# M48_CORE.net
KiCad netlist of a schematic drawn in Altium Designer
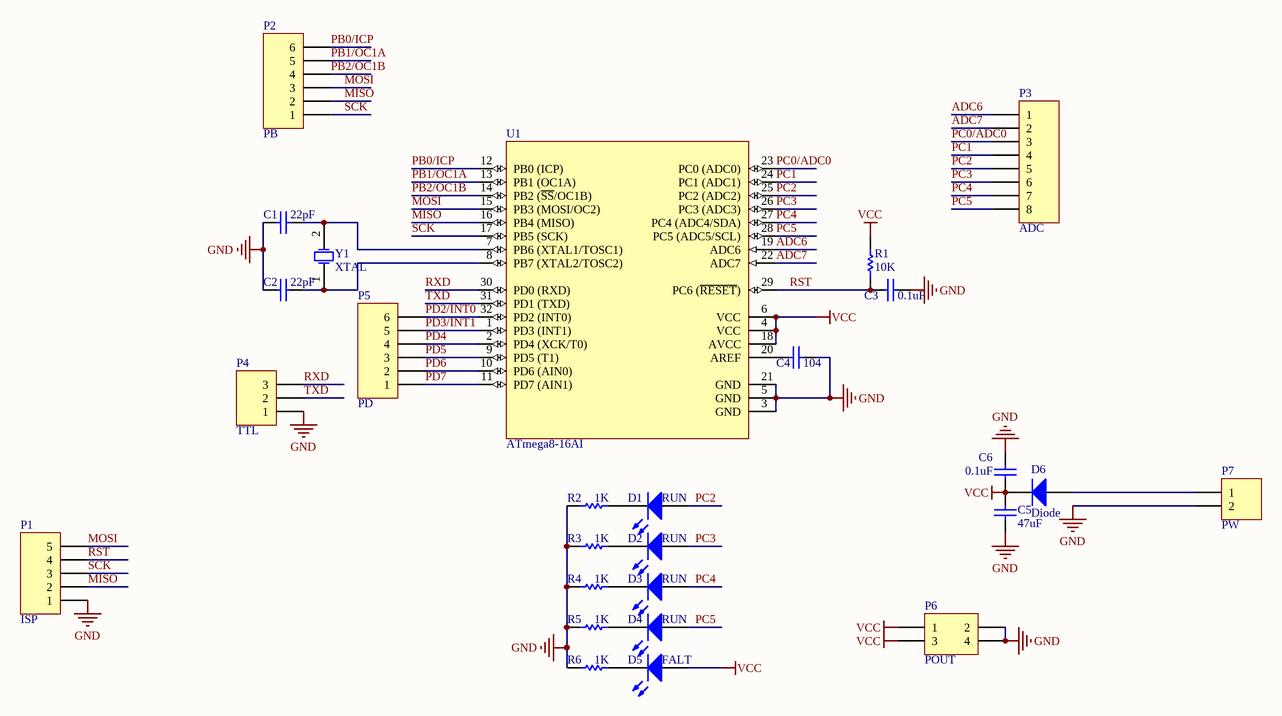
[diagram p0: M48_CORE.SchDoc]

(export (version "E")
  (design (tool "Eeschema 10.0.6"))
  (components
    (comp (ref "C1")
      (value "22pF")
      (footprint "0603")
      (description "Capacitor")
      (fields (field (name "Comment") "Cap") (field (name "PUBLISHER") "Altium Limited"))
      (libsource (lib "Miscellaneous Devices") (part "Cap"))
    )
    (comp (ref "C2")
      (value "22pF")
      (footprint "0603")
      (description "Capacitor")
      (fields (field (name "Comment") "Cap") (field (name "PUBLISHER") "Altium Limited"))
      (libsource (lib "Miscellaneous Devices") (part "Cap"))
    )
    (comp (ref "C3")
      (value "0.1uF")
      (footprint "0603")
      (description "Capacitor")
      (fields (field (name "Comment") "Cap") (field (name "PUBLISHER") "Altium Limited"))
      (libsource (lib "Miscellaneous Devices") (part "Cap"))
    )
    (comp (ref "C4")
      (value "104")
      (footprint "0603")
      (description "Capacitor")
      (fields (field (name "Comment") "Cap") (field (name "PUBLISHER") "Altium Limited"))
      (libsource (lib "Miscellaneous Devices") (part "Cap"))
    )
    (comp (ref "C5")
      (value "47uF")
      (footprint "3216[1206]")
      (description "Capacitor")
      (fields (field (name "Comment") "Cap") (field (name "PUBLISHER") "Altium Limited"))
      (libsource (lib "Miscellaneous Devices") (part "Cap"))
    )
    (comp (ref "C6")
      (value "0.1uF")
      (footprint "0603")
      (description "Capacitor")
      (fields (field (name "Comment") "Cap") (field (name "PUBLISHER") "Altium Limited"))
      (libsource (lib "Miscellaneous Devices") (part "Cap"))
    )
    (comp (ref "D1")
      (value "RUN")
      (footprint "0603-LED")
      (description "Typical RED, GREEN, YELLOW, AMBER GaAs LED")
      (fields (field (name "PUBLISHER") "Altium Limited"))
      (libsource (lib "Miscellaneous Devices") (part "LED2"))
    )
    (comp (ref "D2")
      (value "RUN")
      (footprint "0603-LED")
      (description "Typical RED, GREEN, YELLOW, AMBER GaAs LED")
      (fields (field (name "PUBLISHER") "Altium Limited"))
      (libsource (lib "Miscellaneous Devices") (part "LED2"))
    )
    (comp (ref "D3")
      (value "RUN")
      (footprint "0603-LED")
      (description "Typical RED, GREEN, YELLOW, AMBER GaAs LED")
      (fields (field (name "PUBLISHER") "Altium Limited"))
      (libsource (lib "Miscellaneous Devices") (part "LED2"))
    )
    (comp (ref "D4")
      (value "RUN")
      (footprint "0603-LED")
      (description "Typical RED, GREEN, YELLOW, AMBER GaAs LED")
      (fields (field (name "PUBLISHER") "Altium Limited"))
      (libsource (lib "Miscellaneous Devices") (part "LED2"))
    )
    (comp (ref "D5")
      (value "FALT")
      (footprint "0603-LED")
      (description "Typical RED, GREEN, YELLOW, AMBER GaAs LED")
      (fields (field (name "PUBLISHER") "Altium Limited"))
      (libsource (lib "Miscellaneous Devices") (part "LED2"))
    )
    (comp (ref "D6")
      (value "Diode")
      (footprint "SMA")
      (description "Default Diode")
      (fields (field (name "PUBLISHER") "Altium Limited"))
      (libsource (lib "Miscellaneous Devices") (part "Diode"))
    )
    (comp (ref "P1")
      (value "ISP")
      (footprint "HDR1X5")
      (description "Header, 5-Pin")
      (fields (field (name "PUBLISHER") "Altium Limited"))
      (libsource (lib "Miscellaneous Connectors") (part "Header 5"))
    )
    (comp (ref "P2")
      (value "PB")
      (footprint "HDR1X6")
      (description "Header, 6-Pin")
      (fields (field (name "PUBLISHER") "Altium Limited"))
      (libsource (lib "Miscellaneous Connectors") (part "Header 6"))
    )
    (comp (ref "P3")
      (value "ADC")
      (footprint "HDR1X8")
      (description "Header, 8-Pin")
      (fields (field (name "PUBLISHER") "Altium Limited"))
      (libsource (lib "Miscellaneous Connectors") (part "Header 8"))
    )
    (comp (ref "P4")
      (value "TTL")
      (footprint "HDR1X3")
      (description "Header, 3-Pin")
      (fields (field (name "PUBLISHER") "Altium Limited"))
      (libsource (lib "Miscellaneous Connectors") (part "Header 3"))
    )
    (comp (ref "P5")
      (value "PD")
      (footprint "HDR1X6")
      (description "Header, 6-Pin")
      (fields (field (name "PUBLISHER") "Altium Limited"))
      (libsource (lib "Miscellaneous Connectors") (part "Header 6"))
    )
    (comp (ref "P6")
      (value "POUT")
      (footprint "HDR2X2")
      (description "Header, 2-Pin, Dual row, Right Angle")
      (fields (field (name "PUBLISHER") "Altium Limited"))
      (libsource (lib "Miscellaneous Connectors") (part "Header 2X2H"))
    )
    (comp (ref "P7")
      (value "PW")
      (footprint "XH2.54-2P")
      (description "Header, 2-Pin")
      (fields (field (name "PUBLISHER") "Altium Limited"))
      (libsource (lib "Miscellaneous Connectors") (part "Header 2"))
    )
    (comp (ref "R1")
      (value "10K")
      (footprint "0603")
      (description "Resistor")
      (fields (field (name "Comment") "Res1") (field (name "PUBLISHER") "Altium Limited"))
      (libsource (lib "Miscellaneous Devices") (part "Res1"))
    )
    (comp (ref "R2")
      (value "1K")
      (footprint "0603")
      (description "Resistor")
      (fields (field (name "Comment") "Res1") (field (name "PUBLISHER") "Altium Limited"))
      (libsource (lib "Miscellaneous Devices") (part "Res1"))
    )
    (comp (ref "R3")
      (value "1K")
      (footprint "0603")
      (description "Resistor")
      (fields (field (name "Comment") "Res1") (field (name "PUBLISHER") "Altium Limited"))
      (libsource (lib "Miscellaneous Devices") (part "Res1"))
    )
    (comp (ref "R4")
      (value "1K")
      (footprint "0603")
      (description "Resistor")
      (fields (field (name "Comment") "Res1") (field (name "PUBLISHER") "Altium Limited"))
      (libsource (lib "Miscellaneous Devices") (part "Res1"))
    )
    (comp (ref "R5")
      (value "1K")
      (footprint "0603")
      (description "Resistor")
      (fields (field (name "Comment") "Res1") (field (name "PUBLISHER") "Altium Limited"))
      (libsource (lib "Miscellaneous Devices") (part "Res1"))
    )
    (comp (ref "R6")
      (value "1K")
      (footprint "0603")
      (description "Resistor")
      (fields (field (name "Comment") "Res1") (field (name "PUBLISHER") "Altium Limited"))
      (libsource (lib "Miscellaneous Devices") (part "Res1"))
    )
    (comp (ref "U1")
      (value "ATmega8-16AI")
      (footprint "32A_N")
      (description "8-Bit AVR Microcontroller with 8K Bytes of In-System Programmable Flash Memory")
      (fields (field (name "PUBLISHER") "Altium Limited"))
      (libsource (lib "Atmel Microcontroller 8-Bit AVR") (part "ATmega8-16AI"))
    )
    (comp (ref "Y1")
      (value "XTAL")
      (footprint "XT5032")
      (description "Crystal Oscillator")
      (fields (field (name "PUBLISHER") "Altium Limited"))
      (libsource (lib "Miscellaneous Devices") (part "XTAL"))
    )
  )
  (nets
    (net (code "1") (name "/ADC6") (class "Default")
      (node (ref "P3") (pin "1") (pinfunction "1_1") (pintype "passive"))
      (node (ref "U1") (pin "19") (pinfunction "ADC6_19") (pintype "input"))
    )
    (net (code "2") (name "/ADC7") (class "Default")
      (node (ref "P3") (pin "2") (pinfunction "2_2") (pintype "passive"))
      (node (ref "U1") (pin "22") (pinfunction "ADC7_22") (pintype "input"))
    )
    (net (code "3") (name "/MISO") (class "Default")
      (node (ref "P1") (pin "2") (pinfunction "2_2") (pintype "passive"))
      (node (ref "P2") (pin "2") (pinfunction "2_2") (pintype "passive"))
      (node (ref "U1") (pin "16") (pinfunction "PB4_(MISO)_16") (pintype "bidirectional"))
    )
    (net (code "4") (name "/MOSI") (class "Default")
      (node (ref "P1") (pin "5") (pinfunction "5_5") (pintype "passive"))
      (node (ref "P2") (pin "3") (pinfunction "3_3") (pintype "passive"))
      (node (ref "U1") (pin "15") (pinfunction "PB3_(MOSI/OC2)_15") (pintype "bidirectional"))
    )
    (net (code "5") (name "/PB0{slash}ICP") (class "Default")
      (node (ref "P2") (pin "6") (pinfunction "6_6") (pintype "passive"))
      (node (ref "U1") (pin "12") (pinfunction "PB0_(ICP)_12") (pintype "bidirectional"))
    )
    (net (code "6") (name "/PB1{slash}OC1A") (class "Default")
      (node (ref "P2") (pin "5") (pinfunction "5_5") (pintype "passive"))
      (node (ref "U1") (pin "13") (pinfunction "PB1_(OC1A)_13") (pintype "bidirectional"))
    )
    (net (code "7") (name "/PB2{slash}OC1B") (class "Default")
      (node (ref "P2") (pin "4") (pinfunction "4_4") (pintype "passive"))
      (node (ref "U1") (pin "14") (pinfunction "PB2_(~{SS}/OC1B)_14") (pintype "bidirectional"))
    )
    (net (code "8") (name "/PC0{slash}ADC0") (class "Default")
      (node (ref "P3") (pin "3") (pinfunction "3_3") (pintype "passive"))
      (node (ref "U1") (pin "23") (pinfunction "PC0_(ADC0)_23") (pintype "bidirectional"))
    )
    (net (code "9") (name "/PC1") (class "Default")
      (node (ref "P3") (pin "4") (pinfunction "4_4") (pintype "passive"))
      (node (ref "U1") (pin "24") (pinfunction "PC1_(ADC1)_24") (pintype "bidirectional"))
    )
    (net (code "10") (name "/PC2") (class "Default")
      (node (ref "D1") (pin "1") (pinfunction "A_1") (pintype "passive"))
      (node (ref "P3") (pin "5") (pinfunction "5_5") (pintype "passive"))
      (node (ref "U1") (pin "25") (pinfunction "PC2_(ADC2)_25") (pintype "bidirectional"))
    )
    (net (code "11") (name "/PC3") (class "Default")
      (node (ref "D2") (pin "1") (pinfunction "A_1") (pintype "passive"))
      (node (ref "P3") (pin "6") (pinfunction "6_6") (pintype "passive"))
      (node (ref "U1") (pin "26") (pinfunction "PC3_(ADC3)_26") (pintype "bidirectional"))
    )
    (net (code "12") (name "/PC4") (class "Default")
      (node (ref "D3") (pin "1") (pinfunction "A_1") (pintype "passive"))
      (node (ref "P3") (pin "7") (pinfunction "7_7") (pintype "passive"))
      (node (ref "U1") (pin "27") (pinfunction "PC4_(ADC4/SDA)_27") (pintype "bidirectional"))
    )
    (net (code "13") (name "/PC5") (class "Default")
      (node (ref "D4") (pin "1") (pinfunction "A_1") (pintype "passive"))
      (node (ref "P3") (pin "8") (pinfunction "8_8") (pintype "passive"))
      (node (ref "U1") (pin "28") (pinfunction "PC5_(ADC5/SCL)_28") (pintype "bidirectional"))
    )
    (net (code "14") (name "/PD2{slash}INT0") (class "Default")
      (node (ref "P5") (pin "6") (pinfunction "6_6") (pintype "passive"))
      (node (ref "U1") (pin "32") (pinfunction "PD2_(INT0)_32") (pintype "bidirectional"))
    )
    (net (code "15") (name "/PD3{slash}INT1") (class "Default")
      (node (ref "P5") (pin "5") (pinfunction "5_5") (pintype "passive"))
      (node (ref "U1") (pin "1") (pinfunction "PD3_(INT1)_1") (pintype "bidirectional"))
    )
    (net (code "16") (name "/PD4") (class "Default")
      (node (ref "P5") (pin "4") (pinfunction "4_4") (pintype "passive"))
      (node (ref "U1") (pin "2") (pinfunction "PD4_(XCK/T0)_2") (pintype "bidirectional"))
    )
    (net (code "17") (name "/PD5") (class "Default")
      (node (ref "P5") (pin "3") (pinfunction "3_3") (pintype "passive"))
      (node (ref "U1") (pin "9") (pinfunction "PD5_(T1)_9") (pintype "bidirectional"))
    )
    (net (code "18") (name "/PD6") (class "Default")
      (node (ref "P5") (pin "2") (pinfunction "2_2") (pintype "passive"))
      (node (ref "U1") (pin "10") (pinfunction "PD6_(AIN0)_10") (pintype "bidirectional"))
    )
    (net (code "19") (name "/PD7") (class "Default")
      (node (ref "P5") (pin "1") (pinfunction "1_1") (pintype "passive"))
      (node (ref "U1") (pin "11") (pinfunction "PD7_(AIN1)_11") (pintype "bidirectional"))
    )
    (net (code "20") (name "/RST") (class "Default")
      (node (ref "C3") (pin "1") (pinfunction "1_1") (pintype "passive"))
      (node (ref "P1") (pin "4") (pinfunction "4_4") (pintype "passive"))
      (node (ref "R1") (pin "1") (pinfunction "1_1") (pintype "passive"))
      (node (ref "U1") (pin "29") (pinfunction "PC6_(~{RESET})_29") (pintype "bidirectional"))
    )
    (net (code "21") (name "/RXD") (class "Default")
      (node (ref "P4") (pin "3") (pinfunction "3_3") (pintype "passive"))
      (node (ref "U1") (pin "30") (pinfunction "PD0_(RXD)_30") (pintype "bidirectional"))
    )
    (net (code "22") (name "/SCK") (class "Default")
      (node (ref "P1") (pin "3") (pinfunction "3_3") (pintype "passive"))
      (node (ref "P2") (pin "1") (pinfunction "1_1") (pintype "passive"))
      (node (ref "U1") (pin "17") (pinfunction "PB5_(SCK)_17") (pintype "bidirectional"))
    )
    (net (code "23") (name "/TXD") (class "Default")
      (node (ref "P4") (pin "2") (pinfunction "2_2") (pintype "passive"))
      (node (ref "U1") (pin "31") (pinfunction "PD1_(TXD)_31") (pintype "bidirectional"))
    )
    (net (code "24") (name "GND") (class "Default")
      (node (ref "C1") (pin "2") (pinfunction "2_2") (pintype "passive"))
      (node (ref "C2") (pin "2") (pinfunction "2_2") (pintype "passive"))
      (node (ref "C3") (pin "2") (pinfunction "2_2") (pintype "passive"))
      (node (ref "C4") (pin "2") (pinfunction "2_2") (pintype "passive"))
      (node (ref "C5") (pin "1") (pinfunction "1_1") (pintype "passive"))
      (node (ref "C6") (pin "1") (pinfunction "1_1") (pintype "passive"))
      (node (ref "P1") (pin "1") (pinfunction "1_1") (pintype "passive"))
      (node (ref "P4") (pin "1") (pinfunction "1_1") (pintype "passive"))
      (node (ref "P6") (pin "2") (pinfunction "2_2") (pintype "passive"))
      (node (ref "P6") (pin "4") (pinfunction "4_4") (pintype "passive"))
      (node (ref "P7") (pin "2") (pinfunction "2_2") (pintype "passive"))
      (node (ref "R2") (pin "2") (pinfunction "2_2") (pintype "passive"))
      (node (ref "R3") (pin "2") (pinfunction "2_2") (pintype "passive"))
      (node (ref "R4") (pin "2") (pinfunction "2_2") (pintype "passive"))
      (node (ref "R5") (pin "2") (pinfunction "2_2") (pintype "passive"))
      (node (ref "R6") (pin "2") (pinfunction "2_2") (pintype "passive"))
      (node (ref "U1") (pin "21") (pinfunction "GND_21") (pintype "power_in"))
      (node (ref "U1") (pin "3") (pinfunction "GND_3") (pintype "power_in"))
      (node (ref "U1") (pin "5") (pinfunction "GND_5") (pintype "power_in"))
    )
    (net (code "25") (name "Net-(D1-K)") (class "Default")
      (node (ref "D1") (pin "2") (pinfunction "K_2") (pintype "passive"))
      (node (ref "R2") (pin "1") (pinfunction "1_1") (pintype "passive"))
    )
    (net (code "26") (name "Net-(D2-K)") (class "Default")
      (node (ref "D2") (pin "2") (pinfunction "K_2") (pintype "passive"))
      (node (ref "R3") (pin "1") (pinfunction "1_1") (pintype "passive"))
    )
    (net (code "27") (name "Net-(D3-K)") (class "Default")
      (node (ref "D3") (pin "2") (pinfunction "K_2") (pintype "passive"))
      (node (ref "R4") (pin "1") (pinfunction "1_1") (pintype "passive"))
    )
    (net (code "28") (name "Net-(D4-K)") (class "Default")
      (node (ref "D4") (pin "2") (pinfunction "K_2") (pintype "passive"))
      (node (ref "R5") (pin "1") (pinfunction "1_1") (pintype "passive"))
    )
    (net (code "29") (name "Net-(D5-K)") (class "Default")
      (node (ref "D5") (pin "2") (pinfunction "K_2") (pintype "passive"))
      (node (ref "R6") (pin "1") (pinfunction "1_1") (pintype "passive"))
    )
    (net (code "30") (name "Net-(D6-A)") (class "Default")
      (node (ref "D6") (pin "1") (pinfunction "A_1") (pintype "passive"))
      (node (ref "P7") (pin "1") (pinfunction "1_1") (pintype "passive"))
    )
    (net (code "31") (name "Net-(U1-AREF)") (class "Default")
      (node (ref "C4") (pin "1") (pinfunction "1_1") (pintype "passive"))
      (node (ref "U1") (pin "20") (pinfunction "AREF_20") (pintype "passive"))
    )
    (net (code "32") (name "Net-(U1-PB6_(XTAL1{slash}TOSC1))") (class "Default")
      (node (ref "C1") (pin "1") (pinfunction "1_1") (pintype "passive"))
      (node (ref "U1") (pin "7") (pinfunction "PB6_(XTAL1/TOSC1)_7") (pintype "bidirectional"))
      (node (ref "Y1") (pin "2") (pinfunction "OSC2_2") (pintype "passive"))
    )
    (net (code "33") (name "Net-(U1-PB7_(XTAL2{slash}TOSC2))") (class "Default")
      (node (ref "C2") (pin "1") (pinfunction "1_1") (pintype "passive"))
      (node (ref "U1") (pin "8") (pinfunction "PB7_(XTAL2/TOSC2)_8") (pintype "bidirectional"))
      (node (ref "Y1") (pin "1") (pinfunction "OSC1_1") (pintype "passive"))
    )
    (net (code "34") (name "VCC") (class "Default")
      (node (ref "C5") (pin "2") (pinfunction "2_2") (pintype "passive"))
      (node (ref "C6") (pin "2") (pinfunction "2_2") (pintype "passive"))
      (node (ref "D5") (pin "1") (pinfunction "A_1") (pintype "passive"))
      (node (ref "D6") (pin "2") (pinfunction "K_2") (pintype "passive"))
      (node (ref "P6") (pin "1") (pinfunction "1_1") (pintype "passive"))
      (node (ref "P6") (pin "3") (pinfunction "3_3") (pintype "passive"))
      (node (ref "R1") (pin "2") (pinfunction "2_2") (pintype "passive"))
      (node (ref "U1") (pin "18") (pinfunction "AVCC_18") (pintype "power_in"))
      (node (ref "U1") (pin "4") (pinfunction "VCC_4") (pintype "power_in"))
      (node (ref "U1") (pin "6") (pinfunction "VCC_6") (pintype "power_in"))
    )
  )
)
